# mems.net
KiCad netlist of a schematic drawn in Altium Designer
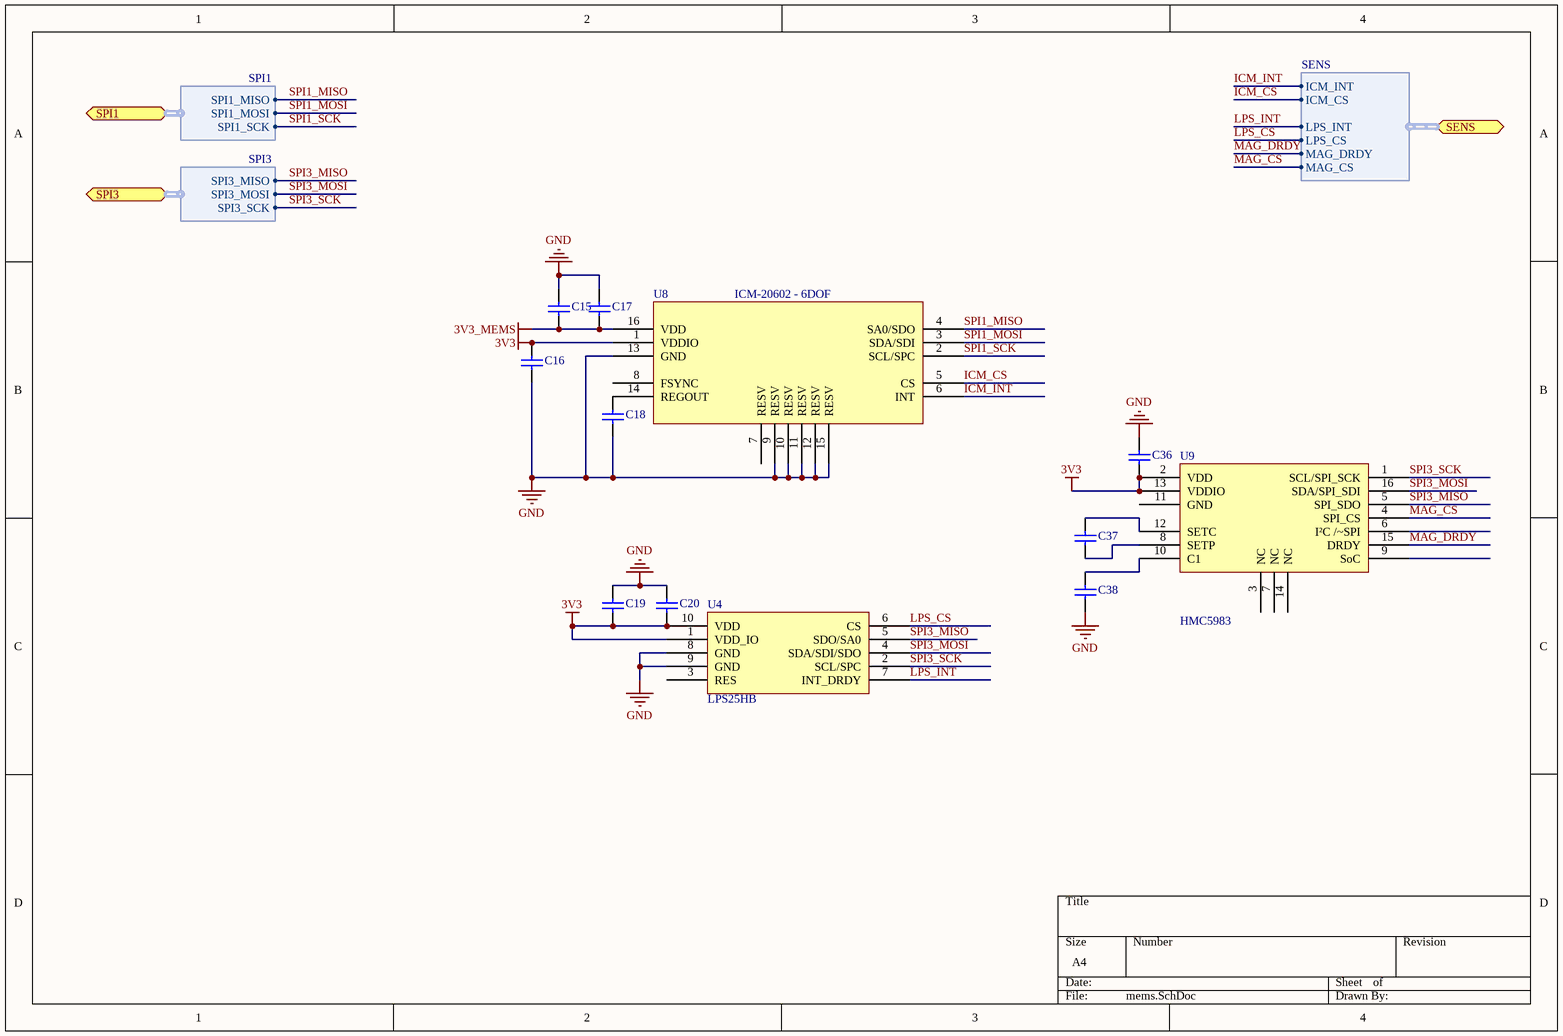
[diagram p0: mems.SchDoc]

(export (version "E")
  (design (tool "Eeschema 10.0.6"))
  (components
    (comp (ref "C15")
      (value "CAP 100nF 35V 0402(1005)")
      (footprint "CAPC0402(1005)60_M")
      (description "CAP 100nF 35V ±10% 0402 (1005 Metric) Thickness 0.6mm SMD")
      (fields (field (name "TOLERANCE") "Â±10%"))
      (libsource (lib "Altium Content Vault") (part "CMP-1034-02075-1"))
    )
    (comp (ref "C16")
      (value "CAP 10nF 35V 0402(1005)")
      (footprint "CAPC0402(1005)60_M")
      (description "CAP 10nF 35V ±10% 0402 (1005 Metric) Thickness 0.6mm SMD")
      (fields (field (name "TOLERANCE") "Â±10%"))
      (libsource (lib "Altium Content Vault") (part "CMP-1034-01883-1"))
    )
    (comp (ref "C17")
      (value "CAP 2.2uF 16V 0603(1608)")
      (footprint "CAPC0603(1608)55_L")
      (description "CAP 2.2uF 16V ±20% 0603 (1608 Metric) Thickness 0.55mm SMD")
      (fields (field (name "TOLERANCE") "Â±20%"))
      (libsource (lib "Altium Content Vault") (part "CAP"))
    )
    (comp (ref "C18")
      (value "CAP 100nF 25V 0402(1005)")
      (footprint "CAPC0402(1005)60_L")
      (description "CAP 100nF 25V ±20% 0402 (1005 Metric) Thickness 0.6mm SMD")
      (fields (field (name "TOLERANCE") "Â±20%"))
      (libsource (lib "Altium Content Vault") (part "CMP-1034-02073-1"))
    )
    (comp (ref "C19")
      (value "CAP 1uF 6.3V 0603(1608)")
      (footprint "CAPC0603(1608)100_L")
      (description "CAP 1uF 6.3V ±20% 0603 (1608 Metric) Thickness 1mm SMD")
      (fields (field (name "TOLERANCE") "Â±20%"))
      (libsource (lib "Altium Content Vault") (part "CAP"))
    )
    (comp (ref "C20")
      (value "CAP 100nF 35V 0402(1005)")
      (footprint "CAPC0402(1005)60_L")
      (description "CAP 100nF 35V ±10% 0402 (1005 Metric) Thickness 0.6mm SMD")
      (fields (field (name "TOLERANCE") "Â±10%"))
      (libsource (lib "Altium Content Vault") (part "CAP"))
    )
    (comp (ref "C36")
      (value "CAP 100nF 35V 0402(1005)")
      (footprint "CAPC0402(1005)60_L")
      (description "CAP 100nF 35V ±10% 0402 (1005 Metric) Thickness 0.6mm SMD")
      (fields (field (name "TOLERANCE") "Â±10%"))
      (libsource (lib "Altium Content Vault") (part "CAP"))
    )
    (comp (ref "C37")
      (value "CAP 220nF 25V 0402(1005)")
      (footprint "CAPC0402(1005)60_L")
      (description "CAP 220nF 25V ±20% 0402 (1005 Metric) Thickness 0.6mm SMD")
      (fields (field (name "TOLERANCE") "Â±20%"))
      (libsource (lib "Altium Content Vault") (part "CAP"))
    )
    (comp (ref "C38")
      (value "CAP 4.7uF 16V 0603(1608)")
      (footprint "CAPC0603(1608)100_L")
      (description "CAP 4.7uF 16V ±20% 0603 (1608 Metric) Thickness 1mm SMD")
      (fields (field (name "TOLERANCE") "Â±20%"))
      (libsource (lib "Altium Content Vault") (part "CMP-1035-02789-1"))
    )
    (comp (ref "U4") (value "LPS25HB") (footprint "HLGA10") (libsource (lib "MyLib") (part "LPS25HB")))
    (comp (ref "U8")
      (value "ICM-20602 - 6DOF")
      (footprint "LCC16")
      (description "ICM-20602")
      (libsource (lib "invensense") (part "ICM-20602"))
    )
    (comp (ref "U9")
      (value "HMC5983")
      (footprint "other:LCC16")
      (description "HMC5983 - 3 axis Compass")
      (libsource (lib "other") (part "HMC5983"))
    )
  )
  (nets
    (net (code "4") (name "/ICM_CS") (class "Default")
      (node (ref "U8") (pin "5") (pinfunction "CS_5") (pintype "passive"))
    )
    (net (code "5") (name "/ICM_INT") (class "Default")
      (node (ref "U8") (pin "6") (pinfunction "INT_6") (pintype "passive"))
    )
    (net (code "6") (name "/LPS_CS") (class "Default")
      (node (ref "U4") (pin "6") (pinfunction "CS_6") (pintype "passive"))
    )
    (net (code "7") (name "/LPS_INT") (class "Default")
      (node (ref "U4") (pin "7") (pinfunction "INT_DRDY_7") (pintype "passive"))
    )
    (net (code "8") (name "/MAG_CS") (class "Default")
      (node (ref "U9") (pin "4") (pinfunction "SPI_CS_4") (pintype "passive"))
    )
    (net (code "9") (name "/MAG_DRDY") (class "Default")
      (node (ref "U9") (pin "15") (pinfunction "DRDY_15") (pintype "passive"))
    )
    (net (code "10") (name "/SPI1_MISO") (class "Default")
      (node (ref "U8") (pin "4") (pinfunction "SA0/SDO_4") (pintype "passive"))
    )
    (net (code "11") (name "/SPI1_MOSI") (class "Default")
      (node (ref "U8") (pin "3") (pinfunction "SDA/SDI_3") (pintype "passive"))
    )
    (net (code "12") (name "/SPI1_SCK") (class "Default")
      (node (ref "U8") (pin "2") (pinfunction "SCL/SPC_2") (pintype "passive"))
    )
    (net (code "13") (name "/SPI3_MISO") (class "Default")
      (node (ref "U4") (pin "5") (pinfunction "SDO/SA0_5") (pintype "passive"))
      (node (ref "U9") (pin "5") (pinfunction "SPI_SDO_5") (pintype "passive"))
    )
    (net (code "14") (name "/SPI3_MOSI") (class "Default")
      (node (ref "U4") (pin "4") (pinfunction "SDA/SDI/SDO_4") (pintype "passive"))
      (node (ref "U9") (pin "16") (pinfunction "SDA/SPI_SDI_16") (pintype "passive"))
    )
    (net (code "15") (name "/SPI3_SCK") (class "Default")
      (node (ref "U4") (pin "2") (pinfunction "SCL/SPC_2") (pintype "passive"))
      (node (ref "U9") (pin "1") (pinfunction "SCL/SPI_SCK_1") (pintype "passive"))
    )
    (net (code "19") (name "3V3") (class "Default")
      (node (ref "C16") (pin "2") (pinfunction "2_2") (pintype "passive"))
      (node (ref "C19") (pin "1") (pinfunction "1_1") (pintype "passive"))
      (node (ref "C20") (pin "1") (pinfunction "1_1") (pintype "passive"))
      (node (ref "C36") (pin "1") (pinfunction "1_1") (pintype "passive"))
      (node (ref "U4") (pin "1") (pinfunction "VDD_IO_1") (pintype "passive"))
      (node (ref "U4") (pin "10") (pinfunction "VDD_10") (pintype "passive"))
      (node (ref "U8") (pin "1") (pinfunction "VDDIO_1") (pintype "passive"))
      (node (ref "U9") (pin "13") (pinfunction "VDDIO_13") (pintype "passive"))
      (node (ref "U9") (pin "2") (pinfunction "VDD_2") (pintype "passive"))
    )
    (net (code "20") (name "3V3_MEMS") (class "Default")
      (node (ref "C15") (pin "1") (pinfunction "1_1") (pintype "passive"))
      (node (ref "C17") (pin "1") (pinfunction "1_1") (pintype "passive"))
      (node (ref "U8") (pin "16") (pinfunction "VDD_16") (pintype "passive"))
    )
    (net (code "21") (name "GND") (class "Default")
      (node (ref "C15") (pin "2") (pinfunction "2_2") (pintype "passive"))
      (node (ref "C16") (pin "1") (pinfunction "1_1") (pintype "passive"))
      (node (ref "C17") (pin "2") (pinfunction "2_2") (pintype "passive"))
      (node (ref "C18") (pin "1") (pinfunction "1_1") (pintype "passive"))
      (node (ref "C19") (pin "2") (pinfunction "2_2") (pintype "passive"))
      (node (ref "C20") (pin "2") (pinfunction "2_2") (pintype "passive"))
      (node (ref "C36") (pin "2") (pinfunction "2_2") (pintype "passive"))
      (node (ref "C38") (pin "1") (pinfunction "1_1") (pintype "passive"))
      (node (ref "U4") (pin "8") (pinfunction "GND_8") (pintype "passive"))
      (node (ref "U4") (pin "9") (pinfunction "GND_9") (pintype "passive"))
      (node (ref "U8") (pin "10") (pinfunction "RESV_10") (pintype "passive"))
      (node (ref "U8") (pin "11") (pinfunction "RESV_11") (pintype "passive"))
      (node (ref "U8") (pin "12") (pinfunction "RESV_12") (pintype "passive"))
      (node (ref "U8") (pin "13") (pinfunction "GND_13") (pintype "passive"))
      (node (ref "U8") (pin "15") (pinfunction "RESV_15") (pintype "passive"))
      (node (ref "U8") (pin "9") (pinfunction "RESV_9") (pintype "passive"))
    )
    (net (code "22") (name "Net-(U8-REGOUT)") (class "Default")
      (node (ref "C18") (pin "2") (pinfunction "2_2") (pintype "passive"))
      (node (ref "U8") (pin "14") (pinfunction "REGOUT_14") (pintype "passive"))
    )
    (net (code "23") (name "Net-(U9-C1)") (class "Default")
      (node (ref "C38") (pin "2") (pinfunction "2_2") (pintype "passive"))
      (node (ref "U9") (pin "10") (pinfunction "C1_10") (pintype "passive"))
    )
    (net (code "24") (name "Net-(U9-SETC)") (class "Default")
      (node (ref "C37") (pin "1") (pinfunction "1_1") (pintype "passive"))
      (node (ref "U9") (pin "12") (pinfunction "SETC_12") (pintype "passive"))
    )
    (net (code "25") (name "Net-(U9-SETP)") (class "Default")
      (node (ref "C37") (pin "2") (pinfunction "2_2") (pintype "passive"))
      (node (ref "U9") (pin "8") (pinfunction "SETP_8") (pintype "passive"))
    )
    (net (code "26") (name "unconnected-(U4-RES-Pad3)") (class "Default")
      (node (ref "U4") (pin "3") (pinfunction "RES_3") (pintype "passive"))
    )
    (net (code "27") (name "unconnected-(U8-FSYNC-Pad8)") (class "Default")
      (node (ref "U8") (pin "8") (pinfunction "FSYNC_8") (pintype "passive"))
    )
    (net (code "28") (name "unconnected-(U8-RESV-Pad7)") (class "Default")
      (node (ref "U8") (pin "7") (pinfunction "RESV_7") (pintype "passive"))
    )
    (net (code "29") (name "unconnected-(U9-GND-Pad11)") (class "Default")
      (node (ref "U9") (pin "11") (pinfunction "GND_11") (pintype "passive"))
    )
    (net (code "30") (name "unconnected-(U9-I²C_{slash}~SPI-Pad6)") (class "Default")
      (node (ref "U9") (pin "6") (pinfunction "I²C_/~SPI_6") (pintype "passive"))
    )
    (net (code "31") (name "unconnected-(U9-NC-Pad3)") (class "Default")
      (node (ref "U9") (pin "3") (pinfunction "NC_3") (pintype "passive"))
    )
    (net (code "32") (name "unconnected-(U9-NC-Pad7)") (class "Default")
      (node (ref "U9") (pin "7") (pinfunction "NC_7") (pintype "passive"))
    )
    (net (code "33") (name "unconnected-(U9-NC-Pad14)") (class "Default")
      (node (ref "U9") (pin "14") (pinfunction "NC_14") (pintype "passive"))
    )
    (net (code "34") (name "unconnected-(U9-SoC-Pad9)") (class "Default")
      (node (ref "U9") (pin "9") (pinfunction "SoC_9") (pintype "passive"))
    )
  )
)
